# mixer2.net
KiCad netlist of a schematic drawn in EAGLE
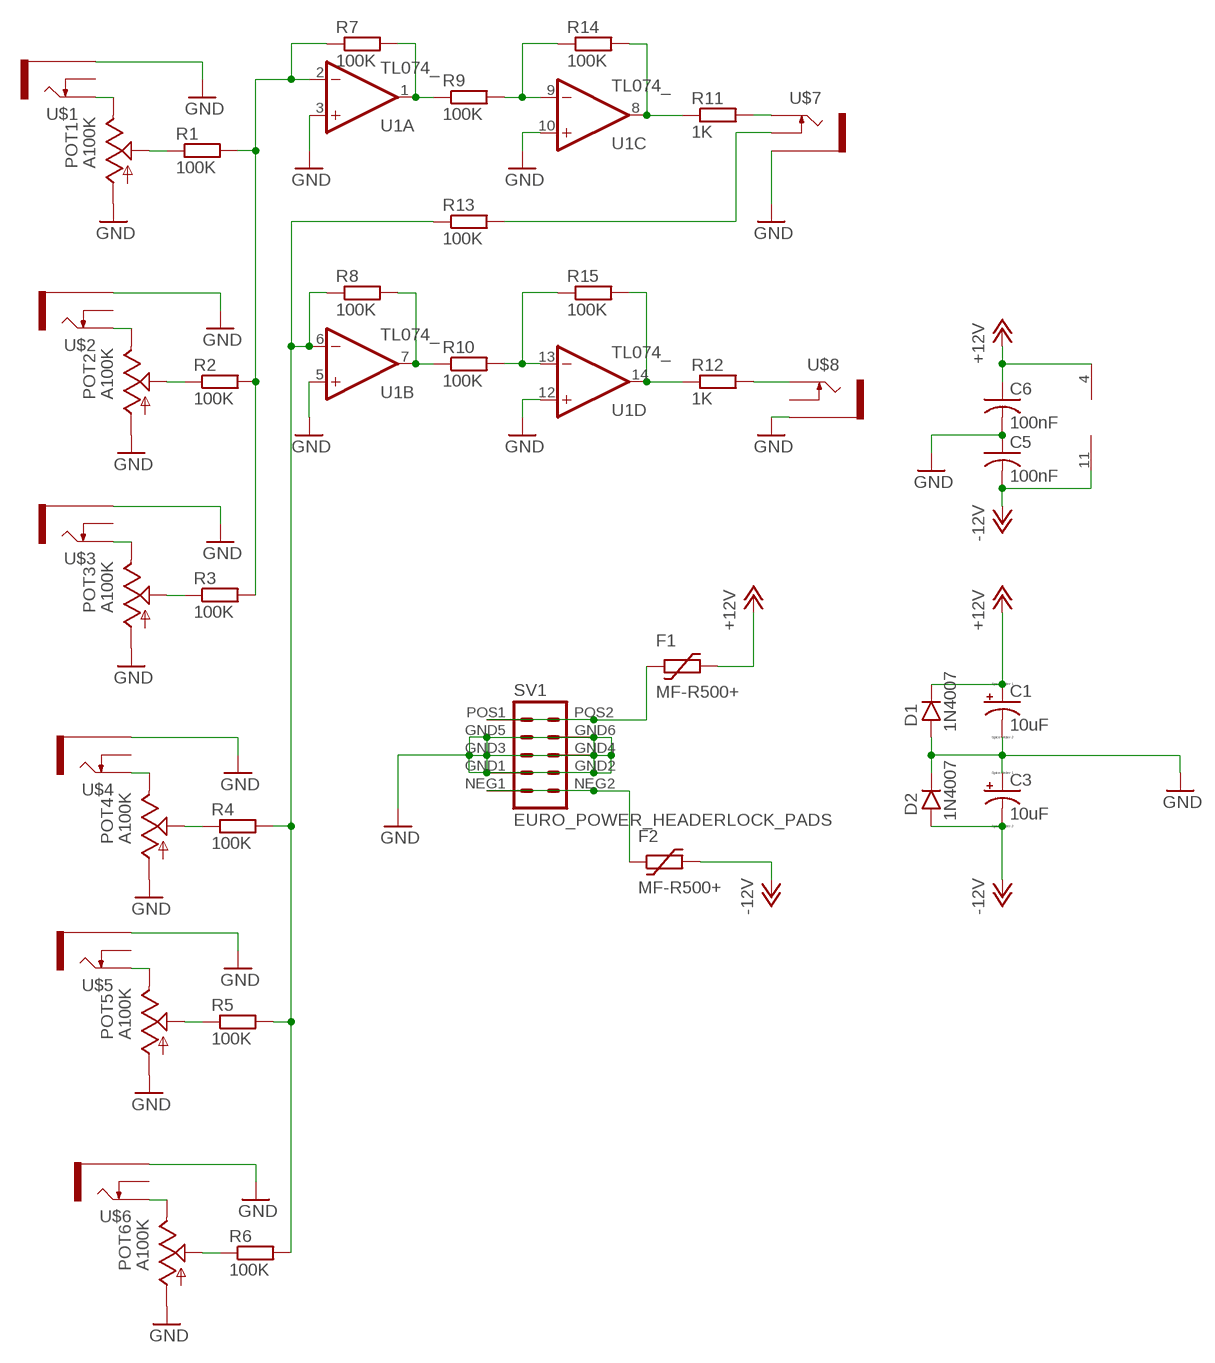
[diagram p0: schematic, sheet 1]

(export (version "E")
  (design (tool "Eeschema 10.0.6"))
  (components
    (comp (ref "C1")
      (value "10uF")
      (footprint "eagle-import:E2,5-7")
      (libsource (lib "eagle-import") (part "CPOL-USE2.5-7"))
    )
    (comp (ref "C3")
      (value "10uF")
      (footprint "eagle-import:E2,5-7")
      (libsource (lib "eagle-import") (part "CPOL-USE2.5-7"))
    )
    (comp (ref "C5")
      (value "100nF")
      (footprint "eagle-import:C075-032X103")
      (libsource (lib "eagle-import") (part "C-US075-032X103"))
    )
    (comp (ref "C6")
      (value "100nF")
      (footprint "eagle-import:C075-032X103")
      (libsource (lib "eagle-import") (part "C-US075-032X103"))
    )
    (comp (ref "D1")
      (value "1N4007")
      (footprint "eagle-import:DO41-3")
      (libsource (lib "eagle-import") (part "1N400X.3"))
    )
    (comp (ref "D2")
      (value "1N4007")
      (footprint "eagle-import:DO41-3")
      (libsource (lib "eagle-import") (part "1N400X.3"))
    )
    (comp (ref "F1")
      (value "MF-R500+")
      (footprint "eagle-import:BOURNS-MF-R")
      (libsource (lib "eagle-import") (part "MF-R500+"))
    )
    (comp (ref "F2")
      (value "MF-R500+")
      (footprint "eagle-import:BOURNS-MF-R")
      (libsource (lib "eagle-import") (part "MF-R500+"))
    )
    (comp (ref "POT1")
      (value "A100K")
      (footprint "eagle-import:9MM_SNAP-IN_POT")
      (libsource (lib "eagle-import") (part "9MM_SNAP-IN_POT_"))
    )
    (comp (ref "POT2")
      (value "A100K")
      (footprint "eagle-import:9MM_SNAP-IN_POT")
      (libsource (lib "eagle-import") (part "9MM_SNAP-IN_POT_"))
    )
    (comp (ref "POT3")
      (value "A100K")
      (footprint "eagle-import:9MM_SNAP-IN_POT")
      (libsource (lib "eagle-import") (part "9MM_SNAP-IN_POT_"))
    )
    (comp (ref "POT4")
      (value "A100K")
      (footprint "eagle-import:9MM_SNAP-IN_POT")
      (libsource (lib "eagle-import") (part "9MM_SNAP-IN_POT_"))
    )
    (comp (ref "POT5")
      (value "A100K")
      (footprint "eagle-import:9MM_SNAP-IN_POT")
      (libsource (lib "eagle-import") (part "9MM_SNAP-IN_POT_"))
    )
    (comp (ref "POT6")
      (value "A100K")
      (footprint "eagle-import:9MM_SNAP-IN_POT")
      (libsource (lib "eagle-import") (part "9MM_SNAP-IN_POT_"))
    )
    (comp (ref "R1")
      (value "100K")
      (footprint "eagle-import:7MM_RESISTOR")
      (libsource (lib "eagle-import") (part "RESISTOR7MM"))
    )
    (comp (ref "R2")
      (value "100K")
      (footprint "eagle-import:7MM_RESISTOR")
      (libsource (lib "eagle-import") (part "RESISTOR7MM"))
    )
    (comp (ref "R3")
      (value "100K")
      (footprint "eagle-import:7MM_RESISTOR")
      (libsource (lib "eagle-import") (part "RESISTOR7MM"))
    )
    (comp (ref "R4")
      (value "100K")
      (footprint "eagle-import:7MM_RESISTOR")
      (libsource (lib "eagle-import") (part "RESISTOR7MM"))
    )
    (comp (ref "R5")
      (value "100K")
      (footprint "eagle-import:7MM_RESISTOR")
      (libsource (lib "eagle-import") (part "RESISTOR7MM"))
    )
    (comp (ref "R6")
      (value "100K")
      (footprint "eagle-import:7MM_RESISTOR")
      (libsource (lib "eagle-import") (part "RESISTOR7MM"))
    )
    (comp (ref "R7")
      (value "100K")
      (footprint "eagle-import:7MM_RESISTOR")
      (libsource (lib "eagle-import") (part "RESISTOR7MM"))
    )
    (comp (ref "R8")
      (value "100K")
      (footprint "eagle-import:7MM_RESISTOR")
      (libsource (lib "eagle-import") (part "RESISTOR7MM"))
    )
    (comp (ref "R9")
      (value "100K")
      (footprint "eagle-import:7MM_RESISTOR")
      (libsource (lib "eagle-import") (part "RESISTOR7MM"))
    )
    (comp (ref "R10")
      (value "100K")
      (footprint "eagle-import:7MM_RESISTOR")
      (libsource (lib "eagle-import") (part "RESISTOR7MM"))
    )
    (comp (ref "R11")
      (value "1K")
      (footprint "eagle-import:7MM_RESISTOR")
      (libsource (lib "eagle-import") (part "RESISTOR7MM"))
    )
    (comp (ref "R12")
      (value "1K")
      (footprint "eagle-import:7MM_RESISTOR")
      (libsource (lib "eagle-import") (part "RESISTOR7MM"))
    )
    (comp (ref "R13")
      (value "100K")
      (footprint "eagle-import:7MM_RESISTOR")
      (libsource (lib "eagle-import") (part "RESISTOR7MM"))
    )
    (comp (ref "R14")
      (value "100K")
      (footprint "eagle-import:7MM_RESISTOR")
      (libsource (lib "eagle-import") (part "RESISTOR7MM"))
    )
    (comp (ref "R15")
      (value "100K")
      (footprint "eagle-import:7MM_RESISTOR")
      (libsource (lib "eagle-import") (part "RESISTOR7MM"))
    )
    (comp (ref "SV1")
      (value "EURO_POWER_HEADERLOCK_PADS")
      (footprint "eagle-import:EURO_PWR_HEADER_LOCK")
      (libsource (lib "eagle-import") (part "EURO_POWER_HEADERLOCK_PADS"))
    )
    (comp (ref "U$1")
      (value "THONKICONNNEW")
      (footprint "eagle-import:WQP-PJ301M-12_JACK")
      (libsource (lib "eagle-import") (part "THONKICONNNEW"))
    )
    (comp (ref "U$2")
      (value "THONKICONNNEW")
      (footprint "eagle-import:WQP-PJ301M-12_JACK")
      (libsource (lib "eagle-import") (part "THONKICONNNEW"))
    )
    (comp (ref "U$3")
      (value "THONKICONNNEW")
      (footprint "eagle-import:WQP-PJ301M-12_JACK")
      (libsource (lib "eagle-import") (part "THONKICONNNEW"))
    )
    (comp (ref "U$4")
      (value "THONKICONNNEW")
      (footprint "eagle-import:WQP-PJ301M-12_JACK")
      (libsource (lib "eagle-import") (part "THONKICONNNEW"))
    )
    (comp (ref "U$5")
      (value "THONKICONNNEW")
      (footprint "eagle-import:WQP-PJ301M-12_JACK")
      (libsource (lib "eagle-import") (part "THONKICONNNEW"))
    )
    (comp (ref "U$6")
      (value "THONKICONNNEW")
      (footprint "eagle-import:WQP-PJ301M-12_JACK")
      (libsource (lib "eagle-import") (part "THONKICONNNEW"))
    )
    (comp (ref "U$7")
      (value "THONKICONNNEW")
      (footprint "eagle-import:WQP-PJ301M-12_JACK")
      (libsource (lib "eagle-import") (part "THONKICONNNEW"))
    )
    (comp (ref "U$8")
      (value "THONKICONNNEW")
      (footprint "eagle-import:WQP-PJ301M-12_JACK")
      (libsource (lib "eagle-import") (part "THONKICONNNEW"))
    )
    (comp (ref "U1")
      (value "TL074_")
      (footprint "eagle-import:DIL14")
      (libsource (lib "eagle-import") (part "TL074_"))
    )
  )
  (nets
    (net (code "1") (name "+12V") (class "Default")
      (node (ref "C1") (pin "+") (pinfunction "+_+") (pintype "passive"))
      (node (ref "C6") (pin "1") (pinfunction "1_1") (pintype "passive"))
      (node (ref "D1") (pin "C") (pinfunction "C_C") (pintype "passive"))
      (node (ref "F1") (pin "P$2") (pinfunction "2_P$2") (pintype "passive"))
      (node (ref "U1") (pin "4") (pinfunction "V+_4") (pintype "power_in"))
    )
    (net (code "2") (name "-12V") (class "Default")
      (node (ref "C3") (pin "-") (pinfunction "-_-") (pintype "passive"))
      (node (ref "C5") (pin "2") (pinfunction "2_2") (pintype "passive"))
      (node (ref "D2") (pin "A") (pinfunction "A_A") (pintype "passive"))
      (node (ref "F2") (pin "P$2") (pinfunction "2_P$2") (pintype "passive"))
      (node (ref "U1") (pin "11") (pinfunction "V-_11") (pintype "power_in"))
    )
    (net (code "3") (name "GND") (class "Default")
      (node (ref "C1") (pin "-") (pinfunction "-_-") (pintype "passive"))
      (node (ref "C3") (pin "+") (pinfunction "+_+") (pintype "passive"))
      (node (ref "C5") (pin "1") (pinfunction "1_1") (pintype "passive"))
      (node (ref "C6") (pin "2") (pinfunction "2_2") (pintype "passive"))
      (node (ref "D1") (pin "A") (pinfunction "A_A") (pintype "passive"))
      (node (ref "D2") (pin "C") (pinfunction "C_C") (pintype "passive"))
      (node (ref "POT1") (pin "1") (pinfunction "A_1") (pintype "passive"))
      (node (ref "POT2") (pin "1") (pinfunction "A_1") (pintype "passive"))
      (node (ref "POT3") (pin "1") (pinfunction "A_1") (pintype "passive"))
      (node (ref "POT4") (pin "1") (pinfunction "A_1") (pintype "passive"))
      (node (ref "POT5") (pin "1") (pinfunction "A_1") (pintype "passive"))
      (node (ref "POT6") (pin "1") (pinfunction "A_1") (pintype "passive"))
      (node (ref "SV1") (pin "GND1") (pinfunction "4_GND1") (pintype "passive"))
      (node (ref "SV1") (pin "GND2") (pinfunction "3_GND2") (pintype "passive"))
      (node (ref "SV1") (pin "GND3") (pinfunction "6_GND3") (pintype "passive"))
      (node (ref "SV1") (pin "GND4") (pinfunction "5_GND4") (pintype "passive"))
      (node (ref "SV1") (pin "GND5") (pinfunction "8_GND5") (pintype "passive"))
      (node (ref "SV1") (pin "GND6") (pinfunction "7_GND6") (pintype "passive"))
      (node (ref "U$1") (pin "P$3_SLEEVE") (pinfunction "SLEEVE_P$3_SLEEVE") (pintype "passive"))
      (node (ref "U$2") (pin "P$3_SLEEVE") (pinfunction "SLEEVE_P$3_SLEEVE") (pintype "passive"))
      (node (ref "U$3") (pin "P$3_SLEEVE") (pinfunction "SLEEVE_P$3_SLEEVE") (pintype "passive"))
      (node (ref "U$4") (pin "P$3_SLEEVE") (pinfunction "SLEEVE_P$3_SLEEVE") (pintype "passive"))
      (node (ref "U$5") (pin "P$3_SLEEVE") (pinfunction "SLEEVE_P$3_SLEEVE") (pintype "passive"))
      (node (ref "U$6") (pin "P$3_SLEEVE") (pinfunction "SLEEVE_P$3_SLEEVE") (pintype "passive"))
      (node (ref "U$7") (pin "P$3_SLEEVE") (pinfunction "SLEEVE_P$3_SLEEVE") (pintype "passive"))
      (node (ref "U$8") (pin "P$3_SLEEVE") (pinfunction "SLEEVE_P$3_SLEEVE") (pintype "passive"))
      (node (ref "U1") (pin "10") (pinfunction "+IN_10") (pintype "input"))
      (node (ref "U1") (pin "12") (pinfunction "+IN_12") (pintype "input"))
      (node (ref "U1") (pin "3") (pinfunction "+IN_3") (pintype "input"))
      (node (ref "U1") (pin "5") (pinfunction "+IN_5") (pintype "input"))
    )
    (net (code "4") (name "Net-(F1-1)") (class "Default")
      (node (ref "F1") (pin "P$1") (pinfunction "1_P$1") (pintype "passive"))
      (node (ref "SV1") (pin "POS1") (pinfunction "10_POS1") (pintype "passive"))
      (node (ref "SV1") (pin "POS2") (pinfunction "9_POS2") (pintype "passive"))
    )
    (net (code "5") (name "Net-(F2-1)") (class "Default")
      (node (ref "F2") (pin "P$1") (pinfunction "1_P$1") (pintype "passive"))
      (node (ref "SV1") (pin "NEG1") (pinfunction "2_NEG1") (pintype "passive"))
      (node (ref "SV1") (pin "NEG2") (pinfunction "1_NEG2") (pintype "passive"))
    )
    (net (code "6") (name "Net-(POT1-E)") (class "Default")
      (node (ref "POT1") (pin "3") (pinfunction "E_3") (pintype "passive"))
      (node (ref "U$1") (pin "P$1_TIP") (pinfunction "TIP_P$1_TIP") (pintype "passive"))
    )
    (net (code "7") (name "Net-(POT1-S)") (class "Default")
      (node (ref "POT1") (pin "2") (pinfunction "S_2") (pintype "passive"))
      (node (ref "R1") (pin "1") (pinfunction "1_1") (pintype "passive"))
    )
    (net (code "8") (name "Net-(POT2-E)") (class "Default")
      (node (ref "POT2") (pin "3") (pinfunction "E_3") (pintype "passive"))
      (node (ref "U$2") (pin "P$1_TIP") (pinfunction "TIP_P$1_TIP") (pintype "passive"))
    )
    (net (code "9") (name "Net-(POT2-S)") (class "Default")
      (node (ref "POT2") (pin "2") (pinfunction "S_2") (pintype "passive"))
      (node (ref "R2") (pin "1") (pinfunction "1_1") (pintype "passive"))
    )
    (net (code "10") (name "Net-(POT3-E)") (class "Default")
      (node (ref "POT3") (pin "3") (pinfunction "E_3") (pintype "passive"))
      (node (ref "U$3") (pin "P$1_TIP") (pinfunction "TIP_P$1_TIP") (pintype "passive"))
    )
    (net (code "11") (name "Net-(POT3-S)") (class "Default")
      (node (ref "POT3") (pin "2") (pinfunction "S_2") (pintype "passive"))
      (node (ref "R3") (pin "1") (pinfunction "1_1") (pintype "passive"))
    )
    (net (code "12") (name "Net-(POT4-E)") (class "Default")
      (node (ref "POT4") (pin "3") (pinfunction "E_3") (pintype "passive"))
      (node (ref "U$4") (pin "P$1_TIP") (pinfunction "TIP_P$1_TIP") (pintype "passive"))
    )
    (net (code "13") (name "Net-(POT4-S)") (class "Default")
      (node (ref "POT4") (pin "2") (pinfunction "S_2") (pintype "passive"))
      (node (ref "R4") (pin "1") (pinfunction "1_1") (pintype "passive"))
    )
    (net (code "14") (name "Net-(POT5-E)") (class "Default")
      (node (ref "POT5") (pin "3") (pinfunction "E_3") (pintype "passive"))
      (node (ref "U$5") (pin "P$1_TIP") (pinfunction "TIP_P$1_TIP") (pintype "passive"))
    )
    (net (code "15") (name "Net-(POT5-S)") (class "Default")
      (node (ref "POT5") (pin "2") (pinfunction "S_2") (pintype "passive"))
      (node (ref "R5") (pin "1") (pinfunction "1_1") (pintype "passive"))
    )
    (net (code "16") (name "Net-(POT6-E)") (class "Default")
      (node (ref "POT6") (pin "3") (pinfunction "E_3") (pintype "passive"))
      (node (ref "U$6") (pin "P$1_TIP") (pinfunction "TIP_P$1_TIP") (pintype "passive"))
    )
    (net (code "17") (name "Net-(POT6-S)") (class "Default")
      (node (ref "POT6") (pin "2") (pinfunction "S_2") (pintype "passive"))
      (node (ref "R6") (pin "1") (pinfunction "1_1") (pintype "passive"))
    )
    (net (code "18") (name "Net-(U$7-SWITCH)") (class "Default")
      (node (ref "R13") (pin "2") (pinfunction "2_2") (pintype "passive"))
      (node (ref "U$7") (pin "P$2_SWITCH") (pinfunction "SWITCH_P$2_SWITCH") (pintype "passive"))
    )
    (net (code "19") (name "Net-(U$7-TIP)") (class "Default")
      (node (ref "R11") (pin "2") (pinfunction "2_2") (pintype "passive"))
      (node (ref "U$7") (pin "P$1_TIP") (pinfunction "TIP_P$1_TIP") (pintype "passive"))
    )
    (net (code "20") (name "Net-(U$8-TIP)") (class "Default")
      (node (ref "R12") (pin "2") (pinfunction "2_2") (pintype "passive"))
      (node (ref "U$8") (pin "P$1_TIP") (pinfunction "TIP_P$1_TIP") (pintype "passive"))
    )
    (net (code "21") (name "Net-(U1A--IN)") (class "Default")
      (node (ref "R1") (pin "2") (pinfunction "2_2") (pintype "passive"))
      (node (ref "R2") (pin "2") (pinfunction "2_2") (pintype "passive"))
      (node (ref "R3") (pin "2") (pinfunction "2_2") (pintype "passive"))
      (node (ref "R7") (pin "1") (pinfunction "1_1") (pintype "passive"))
      (node (ref "U1") (pin "2") (pinfunction "-IN_2") (pintype "input"))
    )
    (net (code "22") (name "Net-(U1A-OUT)") (class "Default")
      (node (ref "R7") (pin "2") (pinfunction "2_2") (pintype "passive"))
      (node (ref "R9") (pin "1") (pinfunction "1_1") (pintype "passive"))
      (node (ref "U1") (pin "1") (pinfunction "OUT_1") (pintype "output"))
    )
    (net (code "23") (name "Net-(U1B--IN)") (class "Default")
      (node (ref "R13") (pin "1") (pinfunction "1_1") (pintype "passive"))
      (node (ref "R4") (pin "2") (pinfunction "2_2") (pintype "passive"))
      (node (ref "R5") (pin "2") (pinfunction "2_2") (pintype "passive"))
      (node (ref "R6") (pin "2") (pinfunction "2_2") (pintype "passive"))
      (node (ref "R8") (pin "1") (pinfunction "1_1") (pintype "passive"))
      (node (ref "U1") (pin "6") (pinfunction "-IN_6") (pintype "input"))
    )
    (net (code "24") (name "Net-(U1B-OUT)") (class "Default")
      (node (ref "R10") (pin "1") (pinfunction "1_1") (pintype "passive"))
      (node (ref "R8") (pin "2") (pinfunction "2_2") (pintype "passive"))
      (node (ref "U1") (pin "7") (pinfunction "OUT_7") (pintype "output"))
    )
    (net (code "25") (name "Net-(U1C--IN)") (class "Default")
      (node (ref "R14") (pin "1") (pinfunction "1_1") (pintype "passive"))
      (node (ref "R9") (pin "2") (pinfunction "2_2") (pintype "passive"))
      (node (ref "U1") (pin "9") (pinfunction "-IN_9") (pintype "input"))
    )
    (net (code "26") (name "Net-(U1C-OUT)") (class "Default")
      (node (ref "R11") (pin "1") (pinfunction "1_1") (pintype "passive"))
      (node (ref "R14") (pin "2") (pinfunction "2_2") (pintype "passive"))
      (node (ref "U1") (pin "8") (pinfunction "OUT_8") (pintype "output"))
    )
    (net (code "27") (name "Net-(U1D--IN)") (class "Default")
      (node (ref "R10") (pin "2") (pinfunction "2_2") (pintype "passive"))
      (node (ref "R15") (pin "1") (pinfunction "1_1") (pintype "passive"))
      (node (ref "U1") (pin "13") (pinfunction "-IN_13") (pintype "input"))
    )
    (net (code "28") (name "Net-(U1D-OUT)") (class "Default")
      (node (ref "R12") (pin "1") (pinfunction "1_1") (pintype "passive"))
      (node (ref "R15") (pin "2") (pinfunction "2_2") (pintype "passive"))
      (node (ref "U1") (pin "14") (pinfunction "OUT_14") (pintype "output"))
    )
    (net (code "29") (name "unconnected-(U$1-SWITCH-PadP$2_SWITCH)") (class "Default")
      (node (ref "U$1") (pin "P$2_SWITCH") (pinfunction "SWITCH_P$2_SWITCH") (pintype "passive"))
    )
    (net (code "30") (name "unconnected-(U$2-SWITCH-PadP$2_SWITCH)") (class "Default")
      (node (ref "U$2") (pin "P$2_SWITCH") (pinfunction "SWITCH_P$2_SWITCH") (pintype "passive"))
    )
    (net (code "31") (name "unconnected-(U$3-SWITCH-PadP$2_SWITCH)") (class "Default")
      (node (ref "U$3") (pin "P$2_SWITCH") (pinfunction "SWITCH_P$2_SWITCH") (pintype "passive"))
    )
    (net (code "32") (name "unconnected-(U$4-SWITCH-PadP$2_SWITCH)") (class "Default")
      (node (ref "U$4") (pin "P$2_SWITCH") (pinfunction "SWITCH_P$2_SWITCH") (pintype "passive"))
    )
    (net (code "33") (name "unconnected-(U$5-SWITCH-PadP$2_SWITCH)") (class "Default")
      (node (ref "U$5") (pin "P$2_SWITCH") (pinfunction "SWITCH_P$2_SWITCH") (pintype "passive"))
    )
    (net (code "34") (name "unconnected-(U$6-SWITCH-PadP$2_SWITCH)") (class "Default")
      (node (ref "U$6") (pin "P$2_SWITCH") (pinfunction "SWITCH_P$2_SWITCH") (pintype "passive"))
    )
    (net (code "35") (name "unconnected-(U$8-SWITCH-PadP$2_SWITCH)") (class "Default")
      (node (ref "U$8") (pin "P$2_SWITCH") (pinfunction "SWITCH_P$2_SWITCH") (pintype "passive"))
    )
  )
)
